# EIB36-JAE.net
KiCad netlist of a schematic drawn in EAGLE
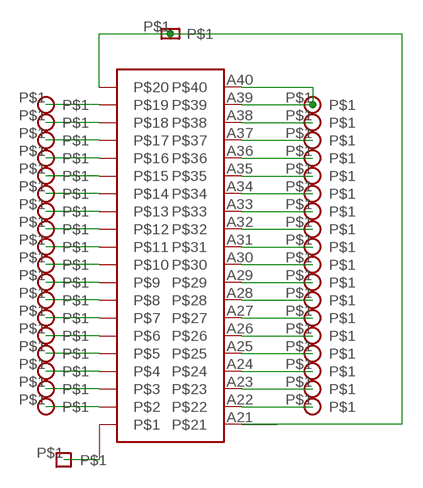
[diagram p0: schematic, sheet 1]

(export (version "E")
  (design (tool "Eeschema 10.0.6"))
  (components
    (comp (ref "U$1")
      (value "WR-40SB-VFH30")
      (footprint "eagle-import:WR-40SB-VFH30")
      (libsource (lib "eagle-import") (part "WR-40SB-VFH30"))
    )
    (comp (ref "U$2")
      (value "EIB-GND-HOLE-PAD-SMALL")
      (footprint "eagle-import:EIB-GND-HOLE-PAD-SMALL")
      (libsource (lib "eagle-import") (part "EIB-GND-HOLE-PAD-SMALL"))
    )
    (comp (ref "U$3")
      (value "EIB-GND-HOLE-PAD")
      (footprint "eagle-import:EIB-GND-HOLE-PAD")
      (libsource (lib "eagle-import") (part "EIB-GND-HOLE-PAD"))
    )
    (comp (ref "U$4")
      (value "EIB-TETRODE-HOLE-PAD")
      (footprint "eagle-import:EIB-TETRODE-HOLE-PAD")
      (libsource (lib "eagle-import") (part "EIB-TETRODE-HOLE-PAD"))
    )
    (comp (ref "U$5")
      (value "EIB-TETRODE-HOLE-PAD")
      (footprint "eagle-import:EIB-TETRODE-HOLE-PAD")
      (libsource (lib "eagle-import") (part "EIB-TETRODE-HOLE-PAD"))
    )
    (comp (ref "U$6")
      (value "EIB-TETRODE-HOLE-PAD")
      (footprint "eagle-import:EIB-TETRODE-HOLE-PAD")
      (libsource (lib "eagle-import") (part "EIB-TETRODE-HOLE-PAD"))
    )
    (comp (ref "U$7")
      (value "EIB-TETRODE-HOLE-PAD")
      (footprint "eagle-import:EIB-TETRODE-HOLE-PAD")
      (libsource (lib "eagle-import") (part "EIB-TETRODE-HOLE-PAD"))
    )
    (comp (ref "U$8")
      (value "EIB-TETRODE-HOLE-PAD")
      (footprint "eagle-import:EIB-TETRODE-HOLE-PAD")
      (libsource (lib "eagle-import") (part "EIB-TETRODE-HOLE-PAD"))
    )
    (comp (ref "U$9")
      (value "EIB-TETRODE-HOLE-PAD")
      (footprint "eagle-import:EIB-TETRODE-HOLE-PAD")
      (libsource (lib "eagle-import") (part "EIB-TETRODE-HOLE-PAD"))
    )
    (comp (ref "U$10")
      (value "EIB-TETRODE-HOLE-PAD")
      (footprint "eagle-import:EIB-TETRODE-HOLE-PAD")
      (libsource (lib "eagle-import") (part "EIB-TETRODE-HOLE-PAD"))
    )
    (comp (ref "U$11")
      (value "EIB-TETRODE-HOLE-PAD")
      (footprint "eagle-import:EIB-TETRODE-HOLE-PAD")
      (libsource (lib "eagle-import") (part "EIB-TETRODE-HOLE-PAD"))
    )
    (comp (ref "U$12")
      (value "EIB-TETRODE-HOLE-PAD")
      (footprint "eagle-import:EIB-TETRODE-HOLE-PAD")
      (libsource (lib "eagle-import") (part "EIB-TETRODE-HOLE-PAD"))
    )
    (comp (ref "U$13")
      (value "EIB-TETRODE-HOLE-PAD")
      (footprint "eagle-import:EIB-TETRODE-HOLE-PAD")
      (libsource (lib "eagle-import") (part "EIB-TETRODE-HOLE-PAD"))
    )
    (comp (ref "U$14")
      (value "EIB-TETRODE-HOLE-PAD")
      (footprint "eagle-import:EIB-TETRODE-HOLE-PAD")
      (libsource (lib "eagle-import") (part "EIB-TETRODE-HOLE-PAD"))
    )
    (comp (ref "U$15")
      (value "EIB-TETRODE-HOLE-PAD")
      (footprint "eagle-import:EIB-TETRODE-HOLE-PAD")
      (libsource (lib "eagle-import") (part "EIB-TETRODE-HOLE-PAD"))
    )
    (comp (ref "U$16")
      (value "EIB-TETRODE-HOLE-PAD")
      (footprint "eagle-import:EIB-TETRODE-HOLE-PAD")
      (libsource (lib "eagle-import") (part "EIB-TETRODE-HOLE-PAD"))
    )
    (comp (ref "U$17")
      (value "EIB-TETRODE-HOLE-PAD")
      (footprint "eagle-import:EIB-TETRODE-HOLE-PAD")
      (libsource (lib "eagle-import") (part "EIB-TETRODE-HOLE-PAD"))
    )
    (comp (ref "U$18")
      (value "EIB-TETRODE-HOLE-PAD")
      (footprint "eagle-import:EIB-TETRODE-HOLE-PAD")
      (libsource (lib "eagle-import") (part "EIB-TETRODE-HOLE-PAD"))
    )
    (comp (ref "U$19")
      (value "EIB-TETRODE-HOLE-PAD")
      (footprint "eagle-import:EIB-TETRODE-HOLE-PAD")
      (libsource (lib "eagle-import") (part "EIB-TETRODE-HOLE-PAD"))
    )
    (comp (ref "U$20")
      (value "EIB-TETRODE-HOLE-PAD")
      (footprint "eagle-import:EIB-TETRODE-HOLE-PAD")
      (libsource (lib "eagle-import") (part "EIB-TETRODE-HOLE-PAD"))
    )
    (comp (ref "U$21")
      (value "EIB-TETRODE-HOLE-PAD")
      (footprint "eagle-import:EIB-TETRODE-HOLE-PAD")
      (libsource (lib "eagle-import") (part "EIB-TETRODE-HOLE-PAD"))
    )
    (comp (ref "U$22")
      (value "EIB-TETRODE-HOLE-PAD")
      (footprint "eagle-import:EIB-TETRODE-HOLE-PAD")
      (libsource (lib "eagle-import") (part "EIB-TETRODE-HOLE-PAD"))
    )
    (comp (ref "U$23")
      (value "EIB-TETRODE-HOLE-PAD")
      (footprint "eagle-import:EIB-TETRODE-HOLE-PAD")
      (libsource (lib "eagle-import") (part "EIB-TETRODE-HOLE-PAD"))
    )
    (comp (ref "U$24")
      (value "EIB-TETRODE-HOLE-PAD")
      (footprint "eagle-import:EIB-TETRODE-HOLE-PAD")
      (libsource (lib "eagle-import") (part "EIB-TETRODE-HOLE-PAD"))
    )
    (comp (ref "U$25")
      (value "EIB-TETRODE-HOLE-PAD")
      (footprint "eagle-import:EIB-TETRODE-HOLE-PAD")
      (libsource (lib "eagle-import") (part "EIB-TETRODE-HOLE-PAD"))
    )
    (comp (ref "U$26")
      (value "EIB-TETRODE-HOLE-PAD")
      (footprint "eagle-import:EIB-TETRODE-HOLE-PAD")
      (libsource (lib "eagle-import") (part "EIB-TETRODE-HOLE-PAD"))
    )
    (comp (ref "U$27")
      (value "EIB-TETRODE-HOLE-PAD")
      (footprint "eagle-import:EIB-TETRODE-HOLE-PAD")
      (libsource (lib "eagle-import") (part "EIB-TETRODE-HOLE-PAD"))
    )
    (comp (ref "U$28")
      (value "EIB-TETRODE-HOLE-PAD")
      (footprint "eagle-import:EIB-TETRODE-HOLE-PAD")
      (libsource (lib "eagle-import") (part "EIB-TETRODE-HOLE-PAD"))
    )
    (comp (ref "U$29")
      (value "EIB-TETRODE-HOLE-PAD")
      (footprint "eagle-import:EIB-TETRODE-HOLE-PAD")
      (libsource (lib "eagle-import") (part "EIB-TETRODE-HOLE-PAD"))
    )
    (comp (ref "U$30")
      (value "EIB-TETRODE-HOLE-PAD")
      (footprint "eagle-import:EIB-TETRODE-HOLE-PAD")
      (libsource (lib "eagle-import") (part "EIB-TETRODE-HOLE-PAD"))
    )
    (comp (ref "U$31")
      (value "EIB-TETRODE-HOLE-PAD")
      (footprint "eagle-import:EIB-TETRODE-HOLE-PAD")
      (libsource (lib "eagle-import") (part "EIB-TETRODE-HOLE-PAD"))
    )
    (comp (ref "U$32")
      (value "EIB-TETRODE-HOLE-PAD")
      (footprint "eagle-import:EIB-TETRODE-HOLE-PAD")
      (libsource (lib "eagle-import") (part "EIB-TETRODE-HOLE-PAD"))
    )
    (comp (ref "U$33")
      (value "EIB-TETRODE-HOLE-PAD")
      (footprint "eagle-import:EIB-TETRODE-HOLE-PAD")
      (libsource (lib "eagle-import") (part "EIB-TETRODE-HOLE-PAD"))
    )
    (comp (ref "U$34")
      (value "EIB-TETRODE-HOLE-PAD")
      (footprint "eagle-import:EIB-TETRODE-HOLE-PAD")
      (libsource (lib "eagle-import") (part "EIB-TETRODE-HOLE-PAD"))
    )
    (comp (ref "U$35")
      (value "EIB-TETRODE-HOLE-PAD")
      (footprint "eagle-import:EIB-TETRODE-HOLE-PAD")
      (libsource (lib "eagle-import") (part "EIB-TETRODE-HOLE-PAD"))
    )
    (comp (ref "U$36")
      (value "EIB-TETRODE-HOLE-PAD")
      (footprint "eagle-import:EIB-TETRODE-HOLE-PAD")
      (libsource (lib "eagle-import") (part "EIB-TETRODE-HOLE-PAD"))
    )
    (comp (ref "U$37")
      (value "EIB-TETRODE-HOLE-PAD")
      (footprint "eagle-import:EIB-TETRODE-HOLE-PAD")
      (libsource (lib "eagle-import") (part "EIB-TETRODE-HOLE-PAD"))
    )
    (comp (ref "U$38")
      (value "EIB-TETRODE-HOLE-PAD")
      (footprint "eagle-import:EIB-TETRODE-HOLE-PAD")
      (libsource (lib "eagle-import") (part "EIB-TETRODE-HOLE-PAD"))
    )
    (comp (ref "U$39")
      (value "EIB-TETRODE-HOLE-PAD")
      (footprint "eagle-import:EIB-TETRODE-HOLE-PAD")
      (libsource (lib "eagle-import") (part "EIB-TETRODE-HOLE-PAD"))
    )
  )
  (nets
    (net (code "1") (name "Net-(U$1-P$1)") (class "Default")
      (node (ref "U$1") (pin "A1") (pinfunction "P$1_A1") (pintype "bidirectional"))
      (node (ref "U$3") (pin "P$1") (pinfunction "P$1_P$1") (pintype "bidirectional"))
    )
    (net (code "2") (name "Net-(U$1-P$2)") (class "Default")
      (node (ref "U$1") (pin "A2") (pinfunction "P$2_A2") (pintype "bidirectional"))
      (node (ref "U$21") (pin "P$1") (pinfunction "P$1_P$1") (pintype "bidirectional"))
    )
    (net (code "3") (name "Net-(U$1-P$3)") (class "Default")
      (node (ref "U$1") (pin "A3") (pinfunction "P$3_A3") (pintype "bidirectional"))
      (node (ref "U$20") (pin "P$1") (pinfunction "P$1_P$1") (pintype "bidirectional"))
    )
    (net (code "4") (name "Net-(U$1-P$4)") (class "Default")
      (node (ref "U$1") (pin "A4") (pinfunction "P$4_A4") (pintype "bidirectional"))
      (node (ref "U$19") (pin "P$1") (pinfunction "P$1_P$1") (pintype "bidirectional"))
    )
    (net (code "5") (name "Net-(U$1-P$5)") (class "Default")
      (node (ref "U$1") (pin "A5") (pinfunction "P$5_A5") (pintype "bidirectional"))
      (node (ref "U$18") (pin "P$1") (pinfunction "P$1_P$1") (pintype "bidirectional"))
    )
    (net (code "6") (name "Net-(U$1-P$6)") (class "Default")
      (node (ref "U$1") (pin "A6") (pinfunction "P$6_A6") (pintype "bidirectional"))
      (node (ref "U$17") (pin "P$1") (pinfunction "P$1_P$1") (pintype "bidirectional"))
    )
    (net (code "7") (name "Net-(U$1-P$7)") (class "Default")
      (node (ref "U$1") (pin "A7") (pinfunction "P$7_A7") (pintype "bidirectional"))
      (node (ref "U$16") (pin "P$1") (pinfunction "P$1_P$1") (pintype "bidirectional"))
    )
    (net (code "8") (name "Net-(U$1-P$8)") (class "Default")
      (node (ref "U$1") (pin "A8") (pinfunction "P$8_A8") (pintype "bidirectional"))
      (node (ref "U$15") (pin "P$1") (pinfunction "P$1_P$1") (pintype "bidirectional"))
    )
    (net (code "9") (name "Net-(U$1-P$9)") (class "Default")
      (node (ref "U$1") (pin "A9") (pinfunction "P$9_A9") (pintype "bidirectional"))
      (node (ref "U$14") (pin "P$1") (pinfunction "P$1_P$1") (pintype "bidirectional"))
    )
    (net (code "10") (name "Net-(U$1-P$10)") (class "Default")
      (node (ref "U$1") (pin "A10") (pinfunction "P$10_A10") (pintype "bidirectional"))
      (node (ref "U$13") (pin "P$1") (pinfunction "P$1_P$1") (pintype "bidirectional"))
    )
    (net (code "11") (name "Net-(U$1-P$11)") (class "Default")
      (node (ref "U$1") (pin "A11") (pinfunction "P$11_A11") (pintype "bidirectional"))
      (node (ref "U$12") (pin "P$1") (pinfunction "P$1_P$1") (pintype "bidirectional"))
    )
    (net (code "12") (name "Net-(U$1-P$12)") (class "Default")
      (node (ref "U$1") (pin "A12") (pinfunction "P$12_A12") (pintype "bidirectional"))
      (node (ref "U$11") (pin "P$1") (pinfunction "P$1_P$1") (pintype "bidirectional"))
    )
    (net (code "13") (name "Net-(U$1-P$13)") (class "Default")
      (node (ref "U$1") (pin "A13") (pinfunction "P$13_A13") (pintype "bidirectional"))
      (node (ref "U$10") (pin "P$1") (pinfunction "P$1_P$1") (pintype "bidirectional"))
    )
    (net (code "14") (name "Net-(U$1-P$14)") (class "Default")
      (node (ref "U$1") (pin "A14") (pinfunction "P$14_A14") (pintype "bidirectional"))
      (node (ref "U$9") (pin "P$1") (pinfunction "P$1_P$1") (pintype "bidirectional"))
    )
    (net (code "15") (name "Net-(U$1-P$15)") (class "Default")
      (node (ref "U$1") (pin "A15") (pinfunction "P$15_A15") (pintype "bidirectional"))
      (node (ref "U$8") (pin "P$1") (pinfunction "P$1_P$1") (pintype "bidirectional"))
    )
    (net (code "16") (name "Net-(U$1-P$16)") (class "Default")
      (node (ref "U$1") (pin "A16") (pinfunction "P$16_A16") (pintype "bidirectional"))
      (node (ref "U$7") (pin "P$1") (pinfunction "P$1_P$1") (pintype "bidirectional"))
    )
    (net (code "17") (name "Net-(U$1-P$17)") (class "Default")
      (node (ref "U$1") (pin "A17") (pinfunction "P$17_A17") (pintype "bidirectional"))
      (node (ref "U$6") (pin "P$1") (pinfunction "P$1_P$1") (pintype "bidirectional"))
    )
    (net (code "18") (name "Net-(U$1-P$18)") (class "Default")
      (node (ref "U$1") (pin "A18") (pinfunction "P$18_A18") (pintype "bidirectional"))
      (node (ref "U$5") (pin "P$1") (pinfunction "P$1_P$1") (pintype "bidirectional"))
    )
    (net (code "19") (name "Net-(U$1-P$19)") (class "Default")
      (node (ref "U$1") (pin "A19") (pinfunction "P$19_A19") (pintype "bidirectional"))
      (node (ref "U$4") (pin "P$1") (pinfunction "P$1_P$1") (pintype "bidirectional"))
    )
    (net (code "20") (name "Net-(U$1-P$20)") (class "Default")
      (node (ref "U$1") (pin "A20") (pinfunction "P$20_A20") (pintype "bidirectional"))
      (node (ref "U$1") (pin "A21") (pinfunction "P$21_A21") (pintype "bidirectional"))
      (node (ref "U$2") (pin "P$1") (pinfunction "P$1_P$1") (pintype "bidirectional"))
    )
    (net (code "21") (name "Net-(U$1-P$22)") (class "Default")
      (node (ref "U$1") (pin "A22") (pinfunction "P$22_A22") (pintype "bidirectional"))
      (node (ref "U$39") (pin "P$1") (pinfunction "P$1_P$1") (pintype "bidirectional"))
    )
    (net (code "22") (name "Net-(U$1-P$23)") (class "Default")
      (node (ref "U$1") (pin "A23") (pinfunction "P$23_A23") (pintype "bidirectional"))
      (node (ref "U$38") (pin "P$1") (pinfunction "P$1_P$1") (pintype "bidirectional"))
    )
    (net (code "23") (name "Net-(U$1-P$24)") (class "Default")
      (node (ref "U$1") (pin "A24") (pinfunction "P$24_A24") (pintype "bidirectional"))
      (node (ref "U$37") (pin "P$1") (pinfunction "P$1_P$1") (pintype "bidirectional"))
    )
    (net (code "24") (name "Net-(U$1-P$25)") (class "Default")
      (node (ref "U$1") (pin "A25") (pinfunction "P$25_A25") (pintype "bidirectional"))
      (node (ref "U$36") (pin "P$1") (pinfunction "P$1_P$1") (pintype "bidirectional"))
    )
    (net (code "25") (name "Net-(U$1-P$26)") (class "Default")
      (node (ref "U$1") (pin "A26") (pinfunction "P$26_A26") (pintype "bidirectional"))
      (node (ref "U$35") (pin "P$1") (pinfunction "P$1_P$1") (pintype "bidirectional"))
    )
    (net (code "26") (name "Net-(U$1-P$27)") (class "Default")
      (node (ref "U$1") (pin "A27") (pinfunction "P$27_A27") (pintype "bidirectional"))
      (node (ref "U$34") (pin "P$1") (pinfunction "P$1_P$1") (pintype "bidirectional"))
    )
    (net (code "27") (name "Net-(U$1-P$28)") (class "Default")
      (node (ref "U$1") (pin "A28") (pinfunction "P$28_A28") (pintype "bidirectional"))
      (node (ref "U$33") (pin "P$1") (pinfunction "P$1_P$1") (pintype "bidirectional"))
    )
    (net (code "28") (name "Net-(U$1-P$29)") (class "Default")
      (node (ref "U$1") (pin "A29") (pinfunction "P$29_A29") (pintype "bidirectional"))
      (node (ref "U$32") (pin "P$1") (pinfunction "P$1_P$1") (pintype "bidirectional"))
    )
    (net (code "29") (name "Net-(U$1-P$30)") (class "Default")
      (node (ref "U$1") (pin "A30") (pinfunction "P$30_A30") (pintype "bidirectional"))
      (node (ref "U$31") (pin "P$1") (pinfunction "P$1_P$1") (pintype "bidirectional"))
    )
    (net (code "30") (name "Net-(U$1-P$31)") (class "Default")
      (node (ref "U$1") (pin "A31") (pinfunction "P$31_A31") (pintype "bidirectional"))
      (node (ref "U$30") (pin "P$1") (pinfunction "P$1_P$1") (pintype "bidirectional"))
    )
    (net (code "31") (name "Net-(U$1-P$32)") (class "Default")
      (node (ref "U$1") (pin "A32") (pinfunction "P$32_A32") (pintype "bidirectional"))
      (node (ref "U$29") (pin "P$1") (pinfunction "P$1_P$1") (pintype "bidirectional"))
    )
    (net (code "32") (name "Net-(U$1-P$33)") (class "Default")
      (node (ref "U$1") (pin "A33") (pinfunction "P$33_A33") (pintype "bidirectional"))
      (node (ref "U$28") (pin "P$1") (pinfunction "P$1_P$1") (pintype "bidirectional"))
    )
    (net (code "33") (name "Net-(U$1-P$34)") (class "Default")
      (node (ref "U$1") (pin "A34") (pinfunction "P$34_A34") (pintype "bidirectional"))
      (node (ref "U$27") (pin "P$1") (pinfunction "P$1_P$1") (pintype "bidirectional"))
    )
    (net (code "34") (name "Net-(U$1-P$35)") (class "Default")
      (node (ref "U$1") (pin "A35") (pinfunction "P$35_A35") (pintype "bidirectional"))
      (node (ref "U$26") (pin "P$1") (pinfunction "P$1_P$1") (pintype "bidirectional"))
    )
    (net (code "35") (name "Net-(U$1-P$36)") (class "Default")
      (node (ref "U$1") (pin "A36") (pinfunction "P$36_A36") (pintype "bidirectional"))
      (node (ref "U$25") (pin "P$1") (pinfunction "P$1_P$1") (pintype "bidirectional"))
    )
    (net (code "36") (name "Net-(U$1-P$37)") (class "Default")
      (node (ref "U$1") (pin "A37") (pinfunction "P$37_A37") (pintype "bidirectional"))
      (node (ref "U$24") (pin "P$1") (pinfunction "P$1_P$1") (pintype "bidirectional"))
    )
    (net (code "37") (name "Net-(U$1-P$38)") (class "Default")
      (node (ref "U$1") (pin "A38") (pinfunction "P$38_A38") (pintype "bidirectional"))
      (node (ref "U$23") (pin "P$1") (pinfunction "P$1_P$1") (pintype "bidirectional"))
    )
    (net (code "38") (name "Net-(U$1-P$39)") (class "Default")
      (node (ref "U$1") (pin "A39") (pinfunction "P$39_A39") (pintype "bidirectional"))
      (node (ref "U$1") (pin "A40") (pinfunction "P$40_A40") (pintype "bidirectional"))
      (node (ref "U$22") (pin "P$1") (pinfunction "P$1_P$1") (pintype "bidirectional"))
    )
  )
)
